# 2126_A_MainBoard_AffichageMatriciel.net
KiCad netlist of a schematic drawn in Altium Designer
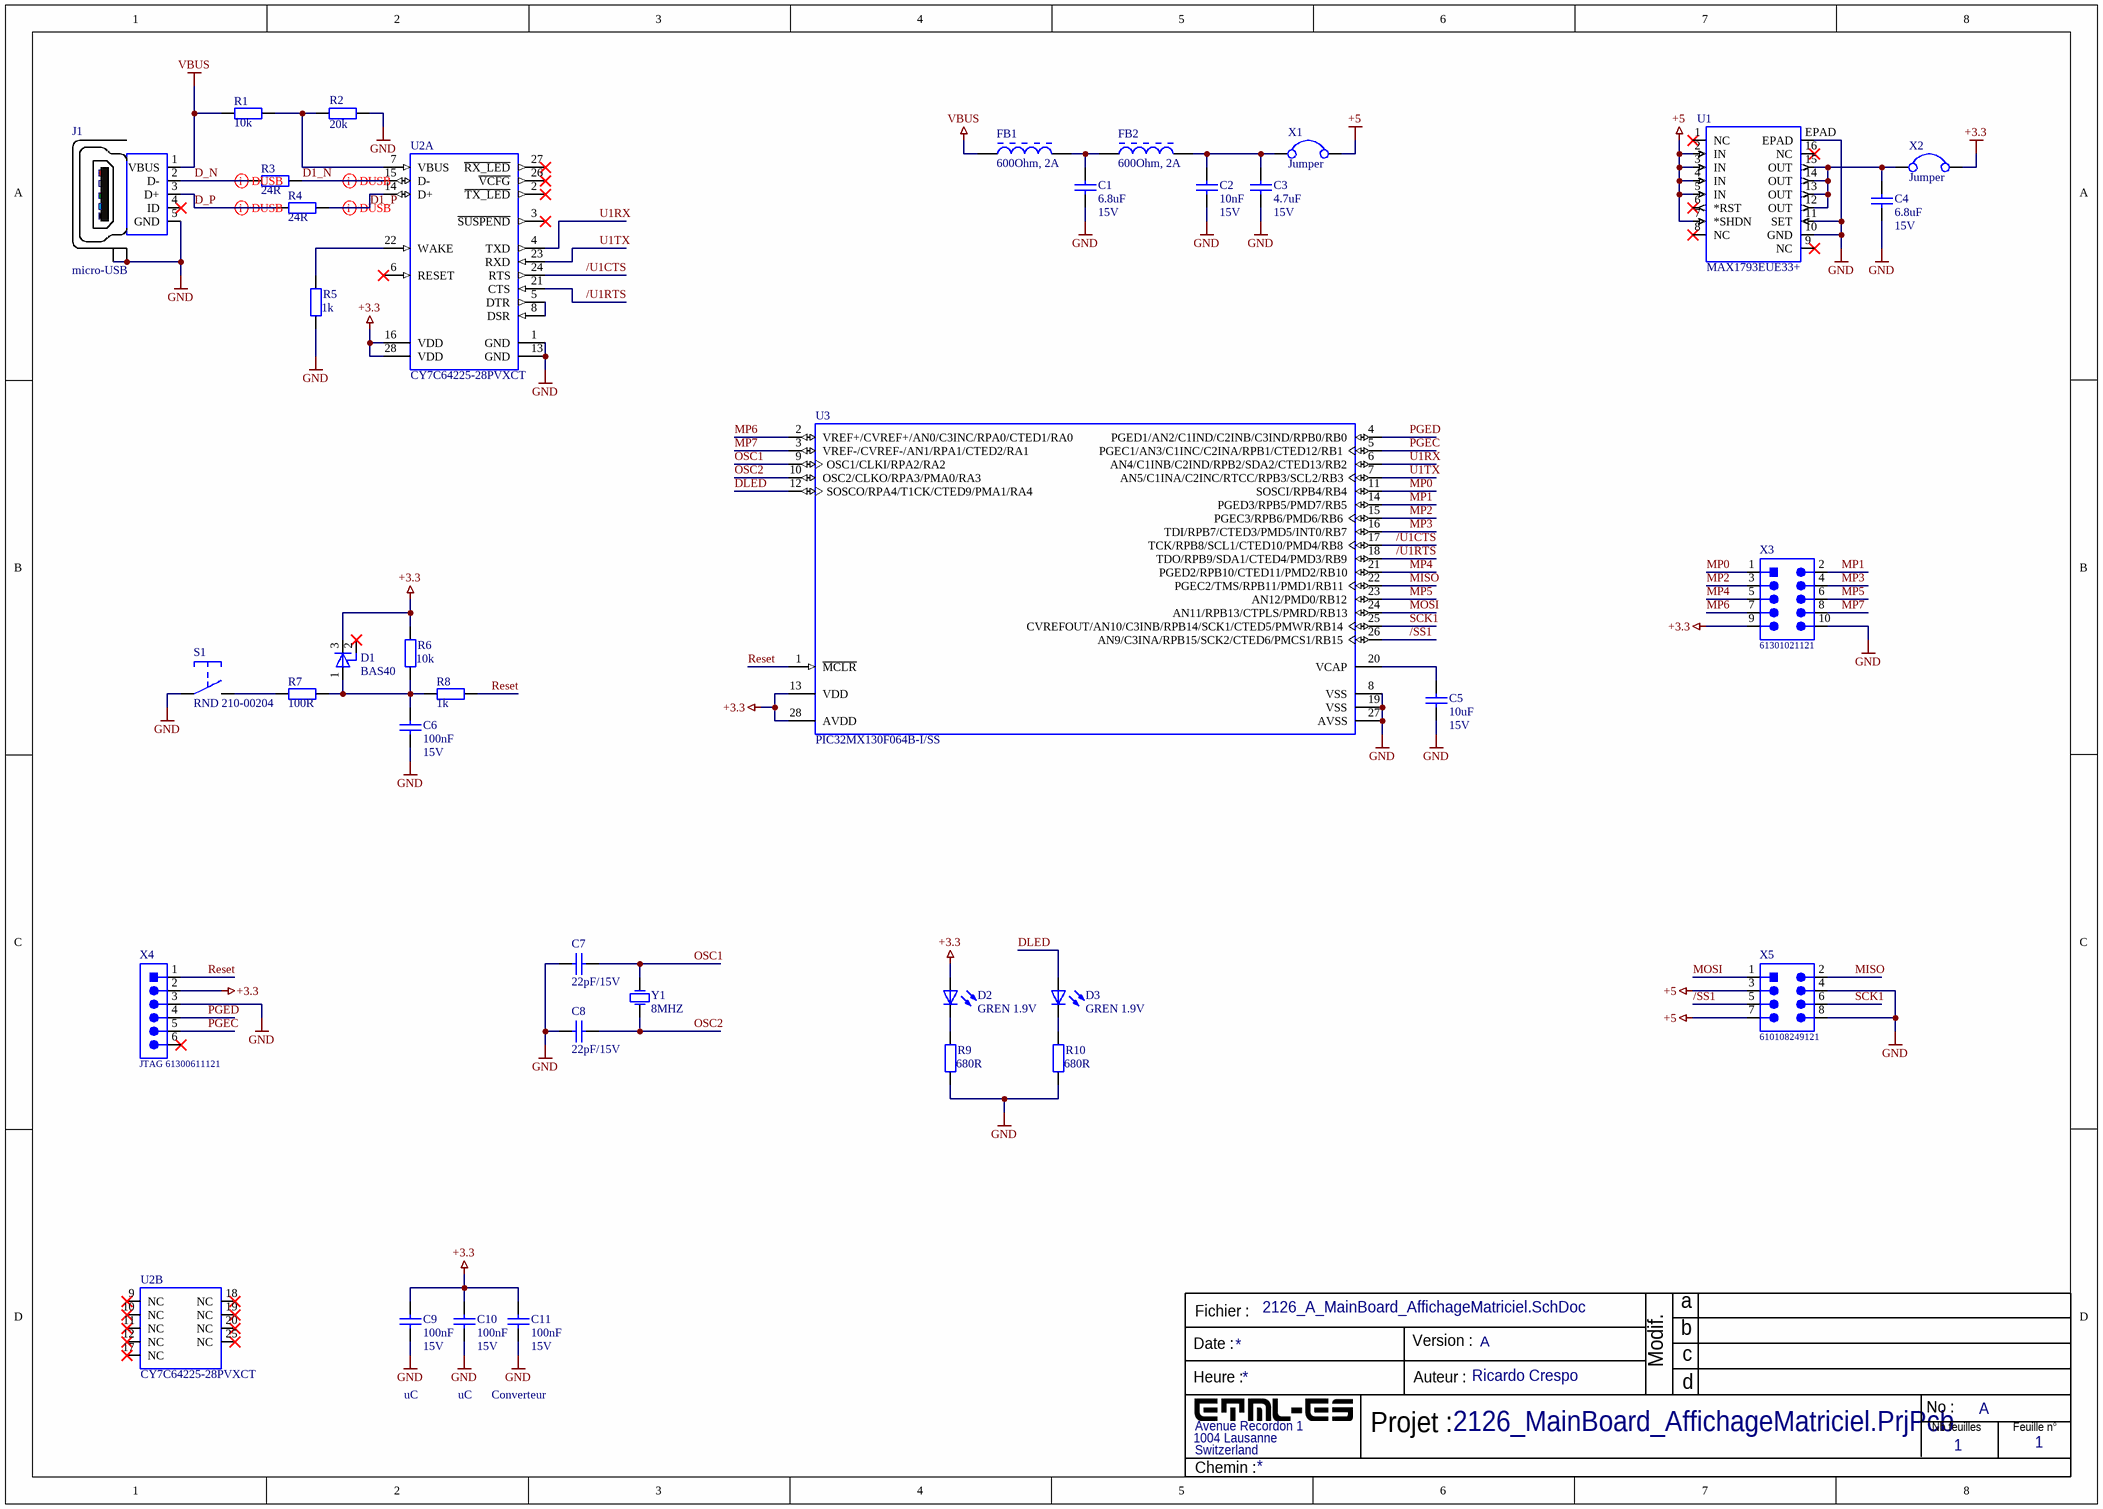
[diagram p0: 2126_A_MainBoard_AffichageMatriciel.SchDoc]

(export (version "E")
  (design (tool "Eeschema 10.0.6"))
  (components
    (comp (ref "C1")
      (value "6.8uF")
      (footprint "CAPC2013X145X48NL20T23")
      (description "VJ0805Y104KNAAT")
      (fields (field (name "MANUFACTURER") "Vitramon"))
      (libsource (lib "2126_AffichageMatriciel") (part "CMP-2007-03167-1"))
    )
    (comp (ref "C2")
      (value "10nF")
      (footprint "CAPC2013X145X48NL20T23")
      (description "VJ0805Y104KNAAT")
      (fields (field (name "MANUFACTURER") "Vitramon"))
      (libsource (lib "2126_AffichageMatriciel") (part "CMP-2007-03167-1"))
    )
    (comp (ref "C3")
      (value "4.7uF")
      (footprint "CAPC2013X145X48NL20T23")
      (description "VJ0805Y104KNAAT")
      (fields (field (name "MANUFACTURER") "Vitramon"))
      (libsource (lib "2126_AffichageMatriciel") (part "CMP-2007-03167-1"))
    )
    (comp (ref "C4")
      (value "6.8uF")
      (footprint "CAPC2013X145X48NL20T23")
      (description "VJ0805Y104KNAAT")
      (fields (field (name "MANUFACTURER") "Vitramon"))
      (libsource (lib "2126_AffichageMatriciel") (part "CMP-2007-03167-1"))
    )
    (comp (ref "C5")
      (value "10uF")
      (footprint "CAPC2013X145X48NL20T23")
      (description "VJ0805Y104KNAAT")
      (fields (field (name "MANUFACTURER") "Vitramon"))
      (libsource (lib "2126_AffichageMatriciel") (part "CMP-2007-03167-1"))
    )
    (comp (ref "C6")
      (value "100nF")
      (footprint "CAPC2013X145X48NL20T23")
      (description "VJ0805Y104KNAAT")
      (fields (field (name "MANUFACTURER") "Vitramon"))
      (libsource (lib "2126_AffichageMatriciel") (part "CMP-2007-03167-1"))
    )
    (comp (ref "C7")
      (value "22pF/15V")
      (footprint "CAPC2013X145X48NL20T23")
      (description "VJ0805Y104KNAAT")
      (fields (field (name "MANUFACTURER") "Vitramon"))
      (libsource (lib "2126_AffichageMatriciel") (part "CMP-2007-03167-1"))
    )
    (comp (ref "C8")
      (value "22pF/15V")
      (footprint "CAPC2013X145X48NL20T23")
      (description "VJ0805Y104KNAAT")
      (fields (field (name "MANUFACTURER") "Vitramon"))
      (libsource (lib "2126_AffichageMatriciel") (part "CMP-2007-03167-1"))
    )
    (comp (ref "C9")
      (value "100nF")
      (footprint "CAPC2013X145X48NL20T23")
      (description "VJ0805Y104KNAAT")
      (fields (field (name "MANUFACTURER") "Vitramon"))
      (libsource (lib "2126_AffichageMatriciel") (part "CMP-2007-03167-1"))
    )
    (comp (ref "C10")
      (value "100nF")
      (footprint "CAPC2013X145X48NL20T23")
      (description "VJ0805Y104KNAAT")
      (fields (field (name "MANUFACTURER") "Vitramon"))
      (libsource (lib "2126_AffichageMatriciel") (part "CMP-2007-03167-1"))
    )
    (comp (ref "C11")
      (value "100nF")
      (footprint "CAPC2013X145X48NL20T23")
      (description "VJ0805Y104KNAAT")
      (fields (field (name "MANUFACTURER") "Vitramon"))
      (libsource (lib "2126_AffichageMatriciel") (part "CMP-2007-03167-1"))
    )
    (comp (ref "D1")
      (value "BAS40")
      (footprint "INF-SOT23_N")
      (description "Silicon Schottky Diode, -55 to 150 degC, SOT23, Reel, Green")
      (fields (field (name "MANUFACTURER") "Infineon"))
      (libsource (lib "2126_AffichageMatriciel") (part "CMP-1182-00023-1"))
    )
    (comp (ref "D2")
      (value "GREN 1.9V")
      (footprint "LED_0805")
      (description "WL-TMRC THT Mono-color Round Color, size 3mm, Bright Green, 2.1V, 40deg")
      (fields (field (name "PART NUMBER") "151031VS04000") (field (name "PUBLISHER") "Wurth Elektronik"))
      (libsource (lib "2126_AffichageMatriciel") (part "151031VS04000_G"))
    )
    (comp (ref "D3")
      (value "GREN 1.9V")
      (footprint "LED_0805")
      (description "WL-TMRC THT Mono-color Round Color, size 3mm, Bright Green, 2.1V, 40deg")
      (fields (field (name "PART NUMBER") "151031VS04000") (field (name "PUBLISHER") "Wurth Elektronik"))
      (libsource (lib "2126_AffichageMatriciel") (part "151031VS04000_G"))
    )
    (comp (ref "FB1")
      (value "600Ohm, 2A")
      (footprint "WE-CBF_1206_High Speed")
      (description "WE-CBF SMT EMI Suppression Ferrite Bead, size 1206, 600Ohm, 2A")
      (fields
        (field (name "MANUFACTURER PART NUMBER") "74279218")
        (field (name "MANUFACTURER") "Wurth Elektronik")
      )
      (libsource (lib "2126_AffichageMatriciel") (part "74279218"))
    )
    (comp (ref "FB2")
      (value "600Ohm, 2A")
      (footprint "WE-CBF_1206_High Speed")
      (description "WE-CBF SMT EMI Suppression Ferrite Bead, size 1206, 600Ohm, 2A")
      (fields
        (field (name "MANUFACTURER PART NUMBER") "74279218")
        (field (name "MANUFACTURER") "Wurth Elektronik")
      )
      (libsource (lib "2126_AffichageMatriciel") (part "74279218"))
    )
    (comp (ref "J1")
      (value "micro-USB")
      (footprint "629105150521")
      (description "WR-COM_USB_Micro Type B_Horizontal_SMT")
      (fields
        (field (name "MANUFACTURER") "Würth Elektronik eiSos GmbH")
        (field (name "PARTNO") "629105150521")
        (field (name "CREATED BY") "Karrer Zheng")
      )
      (libsource (lib "2126_AffichageMatriciel") (part "WR-Communication Connectors 629105150521"))
    )
    (comp (ref "R1")
      (value "10k")
      (footprint "RESC2013X70X40ML20T20")
      (description "10K 0.125W 1% 0805 (2012 Metric)  SMD")
      (fields (field (name "TOLERANCE") "1 %") (field (name "POWER") "0.125 W"))
      (libsource (lib "") (part "CMP-1013-00623-1_2"))
    )
    (comp (ref "R2")
      (value "20k")
      (footprint "RESC2013X70X40ML20T20")
      (description "10K 0.125W 1% 0805 (2012 Metric)  SMD")
      (fields (field (name "TOLERANCE") "1 %") (field (name "POWER") "0.125 W"))
      (libsource (lib "") (part "CMP-1013-00623-1_1"))
    )
    (comp (ref "R3")
      (value "24R")
      (footprint "RESC2013X70X40ML20T20")
      (description "10K 0.125W 1% 0805 (2012 Metric)  SMD")
      (fields (field (name "TOLERANCE") "1 %") (field (name "POWER") "0.125 W"))
      (libsource (lib "") (part "CMP-1013-00623-1_2"))
    )
    (comp (ref "R4")
      (value "24R")
      (footprint "RESC2013X70X40ML20T20")
      (description "10K 0.125W 1% 0805 (2012 Metric)  SMD")
      (fields (field (name "TOLERANCE") "1 %") (field (name "POWER") "0.125 W"))
      (libsource (lib "") (part "CMP-1013-00623-1_2"))
    )
    (comp (ref "R5")
      (value "1k")
      (footprint "RESC2013X70X40ML20T20")
      (description "10K 0.125W 1% 0805 (2012 Metric)  SMD")
      (fields (field (name "TOLERANCE") "1 %") (field (name "POWER") "0.125 W"))
      (libsource (lib "2126_AffichageMatriciel") (part "CMP-1013-00623-1"))
    )
    (comp (ref "R6")
      (value "10k")
      (footprint "RESC2013X70X40ML20T20")
      (description "10K 0.125W 1% 0805 (2012 Metric)  SMD")
      (fields (field (name "TOLERANCE") "1 %") (field (name "POWER") "0.125 W"))
      (libsource (lib "2126_AffichageMatriciel") (part "CMP-1013-00623-1"))
    )
    (comp (ref "R7")
      (value "100R")
      (footprint "RESC2013X70X40ML20T20")
      (description "10K 0.125W 1% 0805 (2012 Metric)  SMD")
      (fields (field (name "TOLERANCE") "1 %") (field (name "POWER") "0.125 W"))
      (libsource (lib "") (part "CMP-1013-00623-1_2"))
    )
    (comp (ref "R8")
      (value "1k")
      (footprint "RESC2013X70X40ML20T20")
      (description "10K 0.125W 1% 0805 (2012 Metric)  SMD")
      (fields (field (name "TOLERANCE") "1 %") (field (name "POWER") "0.125 W"))
      (libsource (lib "") (part "CMP-1013-00623-1_2"))
    )
    (comp (ref "R9")
      (value "680R")
      (footprint "RESC2013X70X40ML20T20")
      (description "10K 0.125W 1% 0805 (2012 Metric)  SMD")
      (fields (field (name "TOLERANCE") "1 %") (field (name "POWER") "0.125 W"))
      (libsource (lib "2126_AffichageMatriciel") (part "CMP-1013-00623-1"))
    )
    (comp (ref "R10")
      (value "680R")
      (footprint "RESC2013X70X40ML20T20")
      (description "10K 0.125W 1% 0805 (2012 Metric)  SMD")
      (fields (field (name "TOLERANCE") "1 %") (field (name "POWER") "0.125 W"))
      (libsource (lib "2126_AffichageMatriciel") (part "CMP-1013-00623-1"))
    )
    (comp (ref "S1")
      (value "RND 210-00204")
      (footprint "PushButton")
      (libsource (lib "2126_AffichageMatriciel") (part "PushBtn"))
    )
    (comp (ref "U1")
      (value "MAX1793EUE33+")
      (footprint "TSOP65P640X110_HS-17N")
      (description "No Description Available")
      (fields (field (name "COPYRIGHT") "Copyright (C) 2021 Ultra Librarian. All rights reserved."))
      (libsource (lib "2126_AffichageMatriciel") (part "MAX1793EUE33+"))
    )
    (comp (ref "U2")
      (value "CY7C64225-28PVXCT")
      (footprint "CYP-PVX28_N")
      (description "USB-to-UART Bridge Controller, 3 to 5.25 V, 0 to 70 degC, 28-Pin SSOP (PVX28), Tape and Reel")
      (fields (field (name "MANUFACTURER") "Cypress"))
      (libsource (lib "") (part "CY7C64225-28PVXCT_1"))
    )
    (comp (ref "U3")
      (value "PIC32MX130F064B-I/SS")
      (footprint "MCHP-SSOP-SS28_N")
      (fields (field (name "MANUFACTURER") "Microchip"))
      (libsource (lib "2126_AffichageMatriciel") (part "PIC32MX130F064B-I/SS"))
    )
    (comp (ref "X1")
      (value "Jumper")
      (footprint "61300211121")
      (libsource (lib "2126_AffichageMatriciel") (part "Jumper"))
    )
    (comp (ref "X2")
      (value "Jumper")
      (footprint "61300211121")
      (libsource (lib "2126_AffichageMatriciel") (part "Jumper"))
    )
    (comp (ref "X3")
      (value "61301021121")
      (footprint "61301021121")
      (description "WR-PHD Pin Header, THT, pitch 2.54mm, Dual Row, Vertical, 10p")
      (fields (field (name "MANUFACTURER") "Wurth Elektronik"))
      (libsource (lib "2126_AffichageMatriciel") (part "61301021121"))
    )
    (comp (ref "X4")
      (value "JTAG 61300611121")
      (footprint "61300611121")
      (description "WR-PHD Pin Header, THT, pitch 2.54mm, Single Row, Vertical, 6p")
      (fields
        (field (name "MANUFACTURER PART NUMBER") "61300611121")
        (field (name "MANUFACTURER") "Wurth Elektronik")
      )
      (libsource (lib "2126_AffichageMatriciel") (part "JTAG 61300611121"))
    )
    (comp (ref "X5")
      (value "610108249121")
      (footprint "610108249121")
      (description "WR-PHD Pin Header, THT, pitch 2.54mm, Dual Row, Angled, 8p")
      (fields
        (field (name "MANUFACTURER PART NUMBER") "61300821021")
        (field (name "MANUFACTURER") "Wurth Elektronik")
      )
      (libsource (lib "2126_AffichageMatriciel") (part "610108249121"))
    )
    (comp (ref "Y1")
      (value "8MHZ")
      (footprint "LFXTAL003151REEL")
      (description "Crystal or Oscillator")
      (fields
        (field (name "MOUSER2 PART NUMBER") "449-LFXTAL003151REEL")
        (field (name "MANUFACTURER_PART_NUMBER") "LFXTAL003151REEL")
      )
      (libsource (lib "2126_AffichageMatriciel") (part "LFXTAL003151REEL"))
    )
  )
  (nets
    (net (code "1") (name "+3.3") (class "Default")
      (node (ref "C10") (pin "2") (pinfunction "2_2") (pintype "passive"))
      (node (ref "C11") (pin "2") (pinfunction "2_2") (pintype "passive"))
      (node (ref "C9") (pin "2") (pinfunction "2_2") (pintype "passive"))
      (node (ref "D1") (pin "3") (pinfunction "K_3") (pintype "passive"))
      (node (ref "D2") (pin "A") (pinfunction "A_A") (pintype "passive"))
      (node (ref "R6") (pin "2") (pinfunction "2_2") (pintype "passive"))
      (node (ref "U2") (pin "16") (pinfunction "VDD_16") (pintype "power_in"))
      (node (ref "U2") (pin "28") (pinfunction "VDD_28") (pintype "power_in"))
      (node (ref "U3") (pin "13") (pinfunction "VDD_13") (pintype "power_in"))
      (node (ref "U3") (pin "28") (pinfunction "AVDD_28") (pintype "power_in"))
      (node (ref "X2") (pin "2") (pinfunction "2_2") (pintype "passive"))
      (node (ref "X3") (pin "9") (pinfunction "9_9") (pintype "passive"))
      (node (ref "X4") (pin "2") (pinfunction "2_2") (pintype "passive"))
    )
    (net (code "2") (name "+5") (class "Default")
      (node (ref "U1") (pin "2") (pinfunction "IN_2") (pintype "input"))
      (node (ref "U1") (pin "3") (pinfunction "IN_3") (pintype "input"))
      (node (ref "U1") (pin "4") (pinfunction "IN_4") (pintype "input"))
      (node (ref "U1") (pin "5") (pinfunction "IN_5") (pintype "input"))
      (node (ref "U1") (pin "7") (pinfunction "*SHDN_7") (pintype "input"))
      (node (ref "X1") (pin "2") (pinfunction "2_2") (pintype "passive"))
      (node (ref "X5") (pin "3") (pinfunction "3_3") (pintype "passive"))
      (node (ref "X5") (pin "7") (pinfunction "7_7") (pintype "passive"))
    )
    (net (code "3") (name "/D1_N") (class "Default")
      (node (ref "R3") (pin "2") (pinfunction "2_2") (pintype "passive"))
      (node (ref "U2") (pin "15") (pinfunction "D-_15") (pintype "bidirectional"))
    )
    (net (code "4") (name "/D1_P") (class "Default")
      (node (ref "R4") (pin "2") (pinfunction "2_2") (pintype "passive"))
      (node (ref "U2") (pin "14") (pinfunction "D+_14") (pintype "bidirectional"))
    )
    (net (code "5") (name "/DLED") (class "Default")
      (node (ref "D3") (pin "A") (pinfunction "A_A") (pintype "passive"))
      (node (ref "U3") (pin "12") (pinfunction "SOSCO/RPA4/T1CK/CTED9/PMA1/RA4_12") (pintype "bidirectional"))
    )
    (net (code "6") (name "/D_N") (class "Default")
      (node (ref "J1") (pin "2") (pinfunction "D-_2") (pintype "passive"))
      (node (ref "R3") (pin "1") (pinfunction "1_1") (pintype "passive"))
    )
    (net (code "7") (name "/D_P") (class "Default")
      (node (ref "J1") (pin "3") (pinfunction "D+_3") (pintype "passive"))
      (node (ref "R4") (pin "1") (pinfunction "1_1") (pintype "passive"))
    )
    (net (code "8") (name "/MISO") (class "Default")
      (node (ref "U3") (pin "22") (pinfunction "PGEC2/TMS/RPB11/PMD1/RB11_22") (pintype "bidirectional"))
      (node (ref "X5") (pin "2") (pinfunction "2_2") (pintype "passive"))
    )
    (net (code "9") (name "/MOSI") (class "Default")
      (node (ref "U3") (pin "24") (pinfunction "AN11/RPB13/CTPLS/PMRD/RB13_24") (pintype "bidirectional"))
      (node (ref "X5") (pin "1") (pinfunction "1_1") (pintype "passive"))
    )
    (net (code "10") (name "/MP0") (class "Default")
      (node (ref "U3") (pin "11") (pinfunction "SOSCI/RPB4/RB4_11") (pintype "bidirectional"))
      (node (ref "X3") (pin "1") (pinfunction "1_1") (pintype "passive"))
    )
    (net (code "11") (name "/MP1") (class "Default")
      (node (ref "U3") (pin "14") (pinfunction "PGED3/RPB5/PMD7/RB5_14") (pintype "bidirectional"))
      (node (ref "X3") (pin "2") (pinfunction "2_2") (pintype "passive"))
    )
    (net (code "12") (name "/MP2") (class "Default")
      (node (ref "U3") (pin "15") (pinfunction "PGEC3/RPB6/PMD6/RB6_15") (pintype "bidirectional"))
      (node (ref "X3") (pin "3") (pinfunction "3_3") (pintype "passive"))
    )
    (net (code "13") (name "/MP3") (class "Default")
      (node (ref "U3") (pin "16") (pinfunction "TDI/RPB7/CTED3/PMD5/INT0/RB7_16") (pintype "bidirectional"))
      (node (ref "X3") (pin "4") (pinfunction "4_4") (pintype "passive"))
    )
    (net (code "14") (name "/MP4") (class "Default")
      (node (ref "U3") (pin "21") (pinfunction "PGED2/RPB10/CTED11/PMD2/RB10_21") (pintype "bidirectional"))
      (node (ref "X3") (pin "5") (pinfunction "5_5") (pintype "passive"))
    )
    (net (code "15") (name "/MP5") (class "Default")
      (node (ref "U3") (pin "23") (pinfunction "AN12/PMD0/RB12_23") (pintype "bidirectional"))
      (node (ref "X3") (pin "6") (pinfunction "6_6") (pintype "passive"))
    )
    (net (code "16") (name "/MP6") (class "Default")
      (node (ref "U3") (pin "2") (pinfunction "VREF+/CVREF+/AN0/C3INC/RPA0/CTED1/RA0_2") (pintype "bidirectional"))
      (node (ref "X3") (pin "7") (pinfunction "7_7") (pintype "passive"))
    )
    (net (code "17") (name "/MP7") (class "Default")
      (node (ref "U3") (pin "3") (pinfunction "VREF-/CVREF-/AN1/RPA1/CTED2/RA1_3") (pintype "bidirectional"))
      (node (ref "X3") (pin "8") (pinfunction "8_8") (pintype "passive"))
    )
    (net (code "18") (name "/OSC1") (class "Default")
      (node (ref "C7") (pin "2") (pinfunction "2_2") (pintype "passive"))
      (node (ref "U3") (pin "9") (pinfunction "OSC1/CLKI/RPA2/RA2_9") (pintype "bidirectional"))
      (node (ref "Y1") (pin "1") (pinfunction "1_1") (pintype "passive"))
    )
    (net (code "19") (name "/OSC2") (class "Default")
      (node (ref "C8") (pin "2") (pinfunction "2_2") (pintype "passive"))
      (node (ref "U3") (pin "10") (pinfunction "OSC2/CLKO/RPA3/PMA0/RA3_10") (pintype "bidirectional"))
      (node (ref "Y1") (pin "2") (pinfunction "2_2") (pintype "passive"))
    )
    (net (code "20") (name "/PGEC") (class "Default")
      (node (ref "U3") (pin "5") (pinfunction "PGEC1/AN3/C1INC/C2INA/RPB1/CTED12/RB1_5") (pintype "bidirectional"))
      (node (ref "X4") (pin "5") (pinfunction "5_5") (pintype "passive"))
    )
    (net (code "21") (name "/PGED") (class "Default")
      (node (ref "U3") (pin "4") (pinfunction "PGED1/AN2/C1IND/C2INB/C3IND/RPB0/RB0_4") (pintype "bidirectional"))
      (node (ref "X4") (pin "4") (pinfunction "4_4") (pintype "passive"))
    )
    (net (code "22") (name "/Reset") (class "Default")
      (node (ref "R8") (pin "2") (pinfunction "2_2") (pintype "passive"))
      (node (ref "U3") (pin "1") (pinfunction "~{MCLR}_1") (pintype "input"))
      (node (ref "X4") (pin "1") (pinfunction "1_1") (pintype "passive"))
    )
    (net (code "23") (name "/SCK1") (class "Default")
      (node (ref "U3") (pin "25") (pinfunction "CVREFOUT/AN10/C3INB/RPB14/SCK1/CTED5/PMWR/RB14_25") (pintype "bidirectional"))
      (node (ref "X5") (pin "6") (pinfunction "6_6") (pintype "passive"))
    )
    (net (code "24") (name "/U1RX") (class "Default")
      (node (ref "U2") (pin "4") (pinfunction "TXD_4") (pintype "output"))
      (node (ref "U3") (pin "6") (pinfunction "AN4/C1INB/C2IND/RPB2/SDA2/CTED13/RB2_6") (pintype "bidirectional"))
    )
    (net (code "25") (name "/U1TX") (class "Default")
      (node (ref "U2") (pin "23") (pinfunction "RXD_23") (pintype "input"))
      (node (ref "U3") (pin "7") (pinfunction "AN5/C1INA/C2INC/RTCC/RPB3/SCL2/RB3_7") (pintype "bidirectional"))
    )
    (net (code "26") (name "/{slash}SS1") (class "Default")
      (node (ref "U3") (pin "26") (pinfunction "AN9/C3INA/RPB15/SCK2/CTED6/PMCS1/RB15_26") (pintype "bidirectional"))
      (node (ref "X5") (pin "5") (pinfunction "5_5") (pintype "passive"))
    )
    (net (code "27") (name "/{slash}U1CTS") (class "Default")
      (node (ref "U2") (pin "24") (pinfunction "RTS_24") (pintype "output"))
      (node (ref "U3") (pin "17") (pinfunction "TCK/RPB8/SCL1/CTED10/PMD4/RB8_17") (pintype "bidirectional"))
    )
    (net (code "28") (name "/{slash}U1RTS") (class "Default")
      (node (ref "U2") (pin "21") (pinfunction "CTS_21") (pintype "input"))
      (node (ref "U3") (pin "18") (pinfunction "TDO/RPB9/SDA1/CTED4/PMD3/RB9_18") (pintype "bidirectional"))
    )
    (net (code "29") (name "GND") (class "Default")
      (node (ref "C1") (pin "1") (pinfunction "1_1") (pintype "passive"))
      (node (ref "C10") (pin "1") (pinfunction "1_1") (pintype "passive"))
      (node (ref "C11") (pin "1") (pinfunction "1_1") (pintype "passive"))
      (node (ref "C2") (pin "1") (pinfunction "1_1") (pintype "passive"))
      (node (ref "C3") (pin "1") (pinfunction "1_1") (pintype "passive"))
      (node (ref "C4") (pin "1") (pinfunction "1_1") (pintype "passive"))
      (node (ref "C5") (pin "1") (pinfunction "1_1") (pintype "passive"))
      (node (ref "C6") (pin "1") (pinfunction "1_1") (pintype "passive"))
      (node (ref "C7") (pin "1") (pinfunction "1_1") (pintype "passive"))
      (node (ref "C8") (pin "1") (pinfunction "1_1") (pintype "passive"))
      (node (ref "C9") (pin "1") (pinfunction "1_1") (pintype "passive"))
      (node (ref "J1") (pin "5") (pinfunction "GND_5") (pintype "passive"))
      (node (ref "J1") (pin "Z1") (pinfunction "Shield_Z1") (pintype "passive"))
      (node (ref "J1") (pin "Z2") (pinfunction "Shield_Z2") (pintype "passive"))
      (node (ref "R10") (pin "1") (pinfunction "1_1") (pintype "passive"))
      (node (ref "R2") (pin "1") (pinfunction "1_1") (pintype "passive"))
      (node (ref "R5") (pin "1") (pinfunction "1_1") (pintype "passive"))
      (node (ref "R9") (pin "1") (pinfunction "1_1") (pintype "passive"))
      (node (ref "S1") (pin "1") (pinfunction "1_1") (pintype "passive"))
      (node (ref "U1") (pin "10") (pinfunction "GND_10") (pintype "power_in"))
      (node (ref "U1") (pin "11") (pinfunction "SET_11") (pintype "input"))
      (node (ref "U1") (pin "EPAD") (pinfunction "EPAD_EPAD") (pintype "passive"))
      (node (ref "U2") (pin "1") (pinfunction "GND_1") (pintype "power_in"))
      (node (ref "U2") (pin "13") (pinfunction "GND_13") (pintype "power_in"))
      (node (ref "U3") (pin "19") (pinfunction "VSS_19") (pintype "power_in"))
      (node (ref "U3") (pin "27") (pinfunction "AVSS_27") (pintype "power_in"))
      (node (ref "U3") (pin "8") (pinfunction "VSS_8") (pintype "power_in"))
      (node (ref "X3") (pin "10") (pinfunction "10_10") (pintype "passive"))
      (node (ref "X4") (pin "3") (pinfunction "3_3") (pintype "passive"))
      (node (ref "X5") (pin "4") (pinfunction "4_4") (pintype "passive"))
      (node (ref "X5") (pin "8") (pinfunction "8_8") (pintype "passive"))
    )
    (net (code "30") (name "Net-(C1-Pad2)") (class "Default")
      (node (ref "C1") (pin "2") (pinfunction "2_2") (pintype "passive"))
      (node (ref "FB1") (pin "2") (pinfunction "2_2") (pintype "passive"))
      (node (ref "FB2") (pin "1") (pinfunction "1_1") (pintype "passive"))
    )
    (net (code "31") (name "Net-(C2-Pad2)") (class "Default")
      (node (ref "C2") (pin "2") (pinfunction "2_2") (pintype "passive"))
      (node (ref "C3") (pin "2") (pinfunction "2_2") (pintype "passive"))
      (node (ref "FB2") (pin "2") (pinfunction "2_2") (pintype "passive"))
      (node (ref "X1") (pin "1") (pinfunction "1_1") (pintype "passive"))
    )
    (net (code "32") (name "Net-(C4-Pad2)") (class "Default")
      (node (ref "C4") (pin "2") (pinfunction "2_2") (pintype "passive"))
      (node (ref "U1") (pin "12") (pinfunction "OUT_12") (pintype "output"))
      (node (ref "U1") (pin "13") (pinfunction "OUT_13") (pintype "output"))
      (node (ref "U1") (pin "14") (pinfunction "OUT_14") (pintype "output"))
      (node (ref "U1") (pin "15") (pinfunction "OUT_15") (pintype "output"))
      (node (ref "X2") (pin "1") (pinfunction "1_1") (pintype "passive"))
    )
    (net (code "33") (name "Net-(D1-A)") (class "Default")
      (node (ref "C6") (pin "2") (pinfunction "2_2") (pintype "passive"))
      (node (ref "D1") (pin "1") (pinfunction "A_1") (pintype "passive"))
      (node (ref "R6") (pin "1") (pinfunction "1_1") (pintype "passive"))
      (node (ref "R7") (pin "2") (pinfunction "2_2") (pintype "passive"))
      (node (ref "R8") (pin "1") (pinfunction "1_1") (pintype "passive"))
    )
    (net (code "34") (name "Net-(D2-PadK)") (class "Default")
      (node (ref "D2") (pin "K") (pinfunction "K_K") (pintype "passive"))
      (node (ref "R9") (pin "2") (pinfunction "2_2") (pintype "passive"))
    )
    (net (code "35") (name "Net-(D3-PadK)") (class "Default")
      (node (ref "D3") (pin "K") (pinfunction "K_K") (pintype "passive"))
      (node (ref "R10") (pin "2") (pinfunction "2_2") (pintype "passive"))
    )
    (net (code "36") (name "Net-(R7-Pad1)") (class "Default")
      (node (ref "R7") (pin "1") (pinfunction "1_1") (pintype "passive"))
      (node (ref "S1") (pin "2") (pinfunction "2_2") (pintype "passive"))
    )
    (net (code "37") (name "Net-(U2A-DSR)") (class "Default")
      (node (ref "U2") (pin "5") (pinfunction "DTR_5") (pintype "output"))
      (node (ref "U2") (pin "8") (pinfunction "DSR_8") (pintype "input"))
    )
    (net (code "38") (name "Net-(U2A-VBUS)") (class "Default")
      (node (ref "R1") (pin "2") (pinfunction "2_2") (pintype "passive"))
      (node (ref "R2") (pin "2") (pinfunction "2_2") (pintype "passive"))
      (node (ref "U2") (pin "7") (pinfunction "VBUS_7") (pintype "input"))
    )
    (net (code "39") (name "Net-(U2A-WAKE)") (class "Default")
      (node (ref "R5") (pin "2") (pinfunction "2_2") (pintype "passive"))
      (node (ref "U2") (pin "22") (pinfunction "WAKE_22") (pintype "input"))
    )
    (net (code "40") (name "Net-(U3-VCAP)") (class "Default")
      (node (ref "C5") (pin "2") (pinfunction "2_2") (pintype "passive"))
      (node (ref "U3") (pin "20") (pinfunction "VCAP_20") (pintype "passive"))
    )
    (net (code "41") (name "VBUS") (class "Default")
      (node (ref "FB1") (pin "1") (pinfunction "1_1") (pintype "passive"))
      (node (ref "J1") (pin "1") (pinfunction "VBUS_1") (pintype "passive"))
      (node (ref "R1") (pin "1") (pinfunction "1_1") (pintype "passive"))
    )
    (net (code "42") (name "unconnected-(D1-NC-Pad2)") (class "Default")
      (node (ref "D1") (pin "2") (pinfunction "NC_2") (pintype "passive+no_connect"))
    )
    (net (code "43") (name "unconnected-(J1-ID-Pad4)") (class "Default")
      (node (ref "J1") (pin "4") (pinfunction "ID_4") (pintype "passive+no_connect"))
    )
    (net (code "44") (name "unconnected-(U1-*RST-Pad6)") (class "Default")
      (node (ref "U1") (pin "6") (pinfunction "*RST_6") (pintype "output+no_connect"))
    )
    (net (code "45") (name "unconnected-(U1-NC-Pad1)") (class "Default")
      (node (ref "U1") (pin "1") (pinfunction "NC_1") (pintype "passive+no_connect"))
    )
    (net (code "46") (name "unconnected-(U1-NC-Pad8)") (class "Default")
      (node (ref "U1") (pin "8") (pinfunction "NC_8") (pintype "passive+no_connect"))
    )
    (net (code "47") (name "unconnected-(U1-NC-Pad9)") (class "Default")
      (node (ref "U1") (pin "9") (pinfunction "NC_9") (pintype "passive+no_connect"))
    )
    (net (code "48") (name "unconnected-(U1-NC-Pad16)") (class "Default")
      (node (ref "U1") (pin "16") (pinfunction "NC_16") (pintype "passive+no_connect"))
    )
    (net (code "49") (name "unconnected-(U2A-RESET-Pad6)") (class "Default")
      (node (ref "U2") (pin "6") (pinfunction "RESET_6") (pintype "input+no_connect"))
    )
    (net (code "50") (name "unconnected-(U2A-~{RX_LED}-Pad27)") (class "Default")
      (node (ref "U2") (pin "27") (pinfunction "~{RX_LED}_27") (pintype "output+no_connect"))
    )
    (net (code "51") (name "unconnected-(U2A-~{SUSPEND}-Pad3)") (class "Default")
      (node (ref "U2") (pin "3") (pinfunction "~{SUSPEND}_3") (pintype "output+no_connect"))
    )
    (net (code "52") (name "unconnected-(U2A-~{TX_LED}-Pad2)") (class "Default")
      (node (ref "U2") (pin "2") (pinfunction "~{TX_LED}_2") (pintype "output+no_connect"))
    )
    (net (code "53") (name "unconnected-(U2A-~{VCFG}-Pad26)") (class "Default")
      (node (ref "U2") (pin "26") (pinfunction "~{VCFG}_26") (pintype "output+no_connect"))
    )
    (net (code "54") (name "unconnected-(U2B-NC-Pad9)") (class "Default")
      (node (ref "U2") (pin "9") (pinfunction "NC_9") (pintype "passive+no_connect"))
    )
    (net (code "55") (name "unconnected-(U2B-NC-Pad10)") (class "Default")
      (node (ref "U2") (pin "10") (pinfunction "NC_10") (pintype "passive+no_connect"))
    )
    (net (code "56") (name "unconnected-(U2B-NC-Pad11)") (class "Default")
      (node (ref "U2") (pin "11") (pinfunction "NC_11") (pintype "passive+no_connect"))
    )
    (net (code "57") (name "unconnected-(U2B-NC-Pad12)") (class "Default")
      (node (ref "U2") (pin "12") (pinfunction "NC_12") (pintype "passive+no_connect"))
    )
    (net (code "58") (name "unconnected-(U2B-NC-Pad17)") (class "Default")
      (node (ref "U2") (pin "17") (pinfunction "NC_17") (pintype "passive+no_connect"))
    )
    (net (code "59") (name "unconnected-(U2B-NC-Pad18)") (class "Default")
      (node (ref "U2") (pin "18") (pinfunction "NC_18") (pintype "passive+no_connect"))
    )
    (net (code "60") (name "unconnected-(U2B-NC-Pad19)") (class "Default")
      (node (ref "U2") (pin "19") (pinfunction "NC_19") (pintype "passive+no_connect"))
    )
    (net (code "61") (name "unconnected-(U2B-NC-Pad20)") (class "Default")
      (node (ref "U2") (pin "20") (pinfunction "NC_20") (pintype "passive+no_connect"))
    )
    (net (code "62") (name "unconnected-(U2B-NC-Pad25)") (class "Default")
      (node (ref "U2") (pin "25") (pinfunction "NC_25") (pintype "passive+no_connect"))
    )
    (net (code "63") (name "unconnected-(X4-Pad6)") (class "Default")
      (node (ref "X4") (pin "6") (pinfunction "6_6") (pintype "passive+no_connect"))
    )
  )
)
